# OSD19001_CORE.net
KiCad netlist of a schematic drawn in Altium Designer
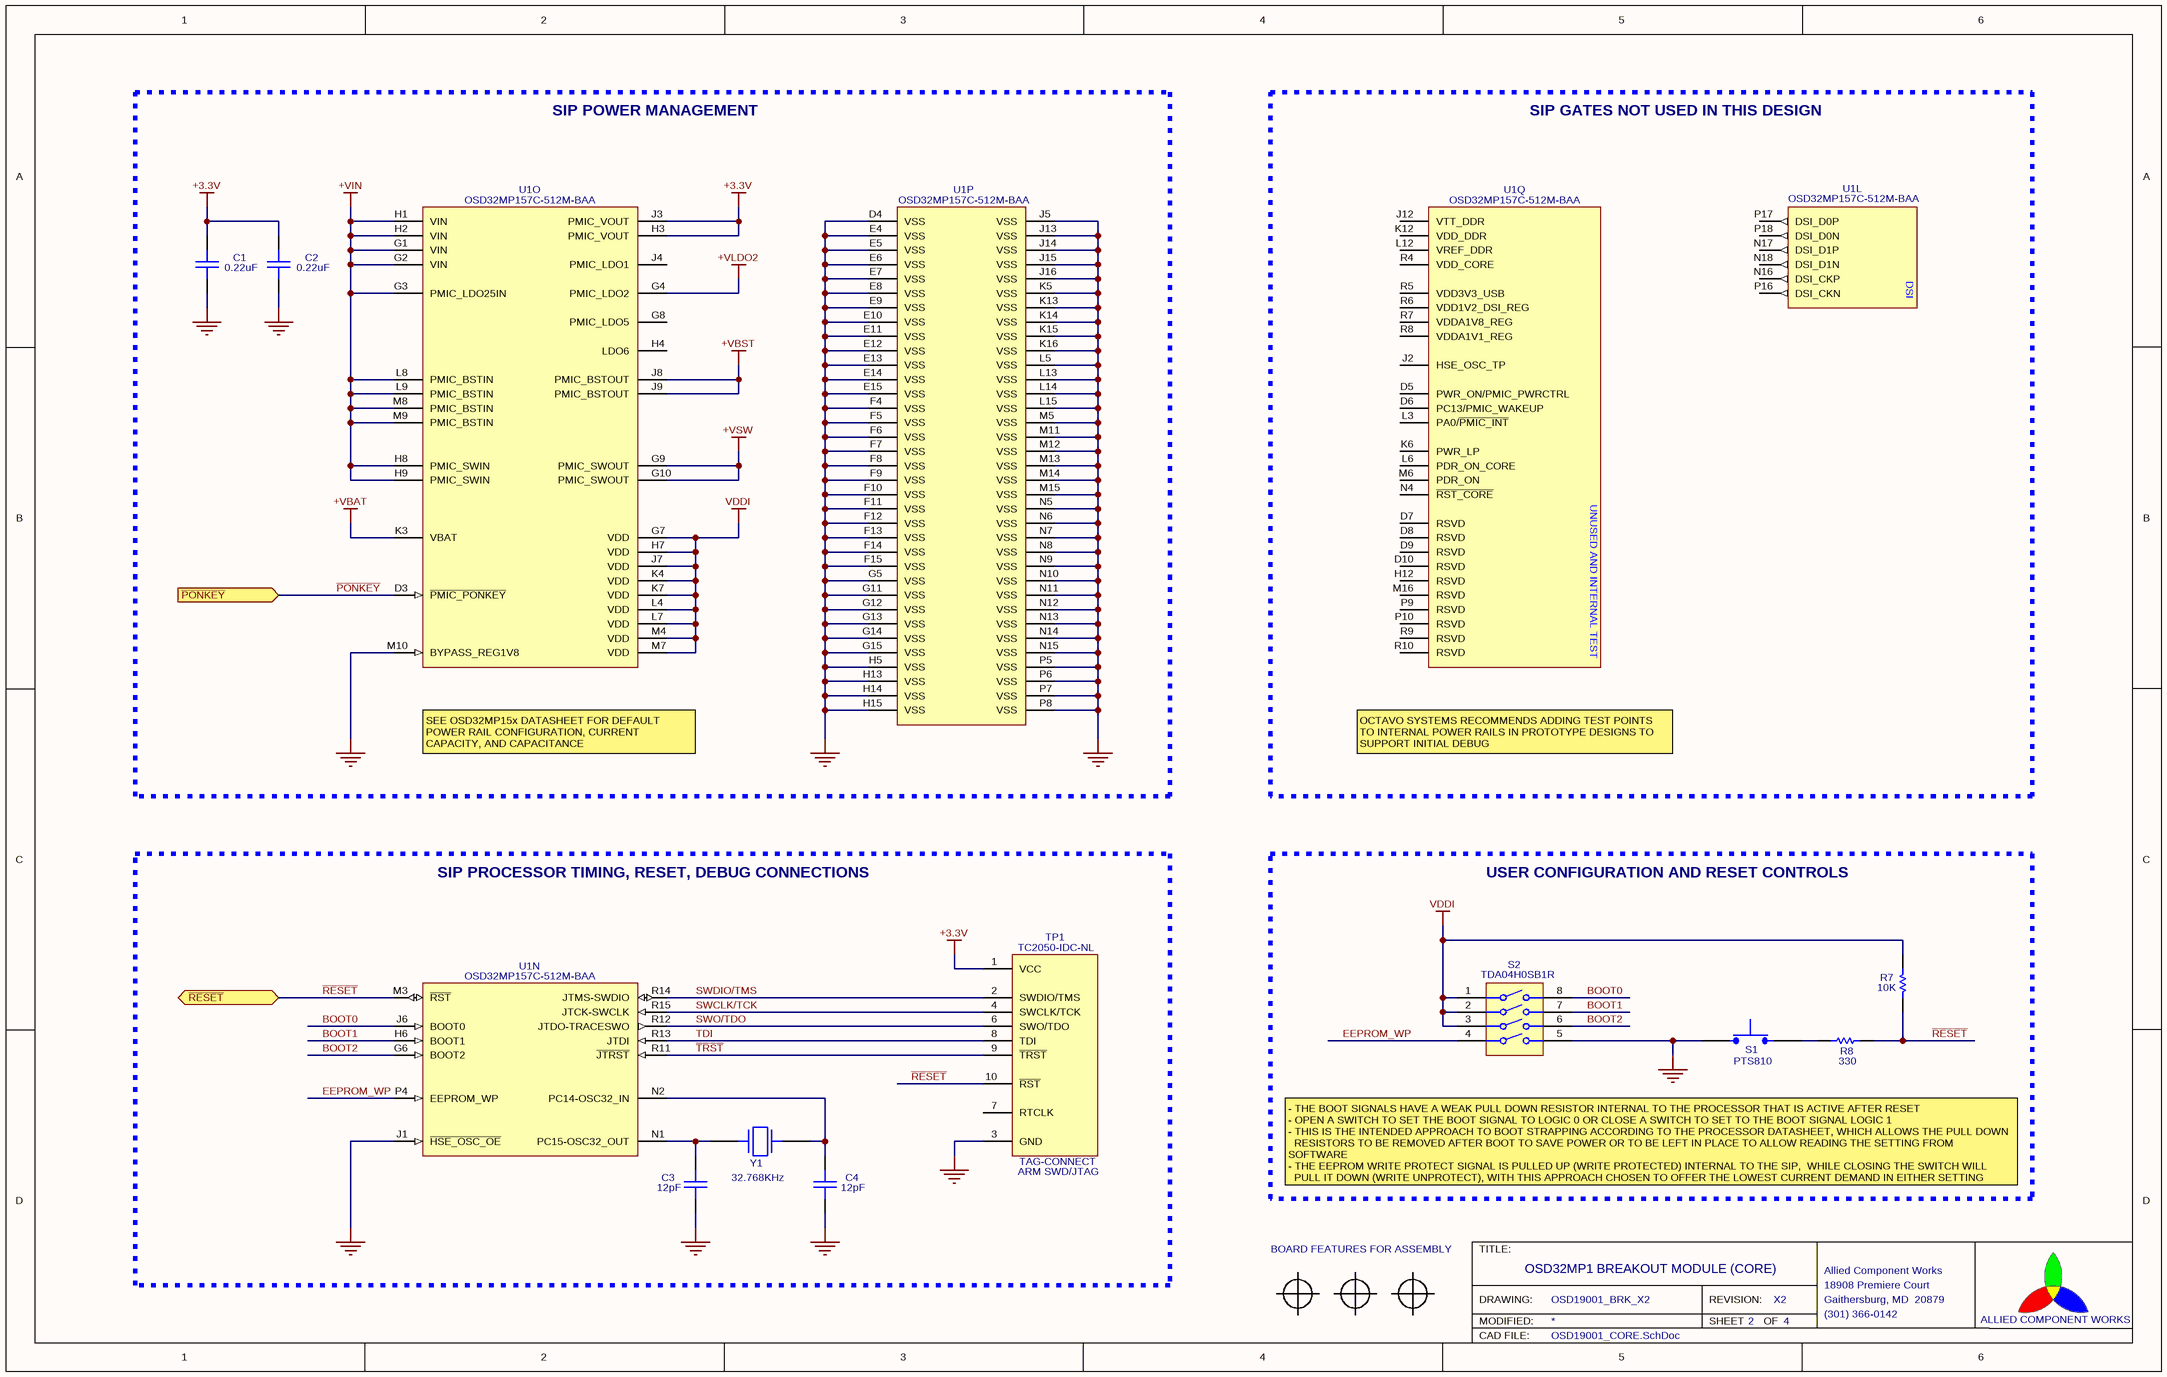
[diagram p0: OSD19001_CORE.SchDoc]

(export (version "E")
  (design (tool "Eeschema 10.0.6"))
  (components
    (comp (ref "C1")
      (value "0.22uF")
      (footprint "LP_0603_HIGH")
      (fields (field (name "TOLERANCE") "10%") (field (name "VOLTAGE") "25V"))
      (libsource (lib "") (part "CERCAP_1"))
    )
    (comp (ref "C2")
      (value "0.22uF")
      (footprint "LP_0603_HIGH")
      (fields (field (name "TOLERANCE") "10%") (field (name "VOLTAGE") "25V"))
      (libsource (lib "") (part "CERCAP_1"))
    )
    (comp (ref "C3")
      (value "12pF")
      (footprint "LP_0402_HIGH")
      (fields (field (name "TOLERANCE") "10%") (field (name "VOLTAGE") "25V"))
      (libsource (lib "ACWPrimitives") (part "CERCAP"))
    )
    (comp (ref "C4")
      (value "12pF")
      (footprint "LP_0402_HIGH")
      (fields (field (name "TOLERANCE") "10%") (field (name "VOLTAGE") "25V"))
      (libsource (lib "ACWPrimitives") (part "CERCAP"))
    )
    (comp (ref "FID1")
      (value "FID")
      (footprint "FID_ROUND_40_TOP")
      (libsource (lib "ACWPrimitives") (part "FIDUCIAL"))
    )
    (comp (ref "FID2")
      (value "FID")
      (footprint "FID_ROUND_40_TOP")
      (libsource (lib "ACWPrimitives") (part "FIDUCIAL"))
    )
    (comp (ref "FID3")
      (value "FID")
      (footprint "FID_ROUND_40_TOP")
      (libsource (lib "ACWPrimitives") (part "FIDUCIAL"))
    )
    (comp (ref "R7")
      (value "10K")
      (footprint "LP_0402_LOW")
      (fields (field (name "TOLERANCE") "5%") (field (name "POWER") "0.1W") (field (name "VOLTAGE") "50V"))
      (libsource (lib "ACWPrimitives") (part "RESISTOR"))
    )
    (comp (ref "R8")
      (value "330")
      (footprint "LP_0402_LOW")
      (fields (field (name "TOLERANCE") "5%") (field (name "POWER") "0.1W") (field (name "VOLTAGE") "50V"))
      (libsource (lib "ACWPrimitives") (part "RESISTOR"))
    )
    (comp (ref "S1")
      (value "PTS810")
      (footprint "C&K_PTS810")
      (description "SPST Tactile Switch, 2 Active Pins")
      (libsource (lib "ACWMisc") (part "TACT_SWITCH"))
    )
    (comp (ref "S2")
      (value "TDA04H0SB1R")
      (footprint "C&K_TDA04")
      (description "Four Position DIP Switch")
      (libsource (lib "ACWMisc") (part "DIP_SW_4"))
    )
    (comp (ref "TP1")
      (value "TC2050-IDC-NL")
      (footprint "TC2050_SITE_NL")
      (description "Tag Connect Site, 10-Pin")
      (libsource (lib "ACWConnectors") (part "TC2050"))
    )
    (comp (ref "U1")
      (value "OSD32MP157C-512M-BAA")
      (footprint "BGA_OCTAVO_SIP_OSD32MP157C")
      (description "Octavo ST Processor SIP")
      (fields (field (name "MANUFACTURER") "Octavo Systems"))
      (libsource (lib "ACWModules") (part "OSD32MP157C"))
    )
    (comp (ref "Y1")
      (value "32.768KHz")
      (footprint "NDK_CRYSTAL_1.5X3.2")
      (description "Crystal")
      (fields (field (name "PARTNUMBER") "NX3215SA-32.768K-STD-MUA-9"))
      (libsource (lib "ACWSemiconductors") (part "CRYSTAL_2PIN"))
    )
  )
  (nets
    (net (code "1") (name "+3.3V") (class "Default")
      (node (ref "C1") (pin "1") (pinfunction "1_1") (pintype "passive"))
      (node (ref "C2") (pin "1") (pinfunction "1_1") (pintype "passive"))
      (node (ref "TP1") (pin "1") (pinfunction "VCC_1") (pintype "passive"))
      (node (ref "U1") (pin "H3") (pinfunction "PMIC_VOUT_H3") (pintype "passive"))
      (node (ref "U1") (pin "J3") (pinfunction "PMIC_VOUT_J3") (pintype "passive"))
    )
    (net (code "2") (name "+VBAT") (class "Default")
      (node (ref "U1") (pin "K3") (pinfunction "VBAT_K3") (pintype "power_in"))
    )
    (net (code "3") (name "+VBST") (class "Default")
      (node (ref "U1") (pin "J8") (pinfunction "PMIC_BSTOUT_J8") (pintype "passive"))
      (node (ref "U1") (pin "J9") (pinfunction "PMIC_BSTOUT_J9") (pintype "passive"))
    )
    (net (code "4") (name "+VIN") (class "Default")
      (node (ref "U1") (pin "G1") (pinfunction "VIN_G1") (pintype "power_in"))
      (node (ref "U1") (pin "G2") (pinfunction "VIN_G2") (pintype "power_in"))
      (node (ref "U1") (pin "G3") (pinfunction "PMIC_LDO25IN_G3") (pintype "power_in"))
      (node (ref "U1") (pin "H1") (pinfunction "VIN_H1") (pintype "power_in"))
      (node (ref "U1") (pin "H2") (pinfunction "VIN_H2") (pintype "power_in"))
      (node (ref "U1") (pin "H8") (pinfunction "PMIC_SWIN_H8") (pintype "passive"))
      (node (ref "U1") (pin "H9") (pinfunction "PMIC_SWIN_H9") (pintype "passive"))
      (node (ref "U1") (pin "L8") (pinfunction "PMIC_BSTIN_L8") (pintype "power_in"))
      (node (ref "U1") (pin "L9") (pinfunction "PMIC_BSTIN_L9") (pintype "power_in"))
      (node (ref "U1") (pin "M8") (pinfunction "PMIC_BSTIN_M8") (pintype "power_in"))
      (node (ref "U1") (pin "M9") (pinfunction "PMIC_BSTIN_M9") (pintype "power_in"))
    )
    (net (code "5") (name "+VLDO2") (class "Default")
      (node (ref "U1") (pin "G4") (pinfunction "PMIC_LDO2_G4") (pintype "passive"))
    )
    (net (code "6") (name "+VSW") (class "Default")
      (node (ref "U1") (pin "G10") (pinfunction "PMIC_SWOUT_G10") (pintype "passive"))
      (node (ref "U1") (pin "G9") (pinfunction "PMIC_SWOUT_G9") (pintype "passive"))
    )
    (net (code "7") (name "/BOOT0") (class "Default")
      (node (ref "S2") (pin "8") (pinfunction "8_8") (pintype "passive"))
      (node (ref "U1") (pin "J6") (pinfunction "BOOT0_J6") (pintype "input"))
    )
    (net (code "8") (name "/BOOT1") (class "Default")
      (node (ref "S2") (pin "7") (pinfunction "7_7") (pintype "passive"))
      (node (ref "U1") (pin "H6") (pinfunction "BOOT1_H6") (pintype "input"))
    )
    (net (code "9") (name "/BOOT2") (class "Default")
      (node (ref "S2") (pin "6") (pinfunction "6_6") (pintype "passive"))
      (node (ref "U1") (pin "G6") (pinfunction "BOOT2_G6") (pintype "input"))
    )
    (net (code "10") (name "/EEPROM_WP") (class "Default")
      (node (ref "S2") (pin "4") (pinfunction "4_4") (pintype "passive"))
      (node (ref "U1") (pin "P4") (pinfunction "EEPROM_WP_P4") (pintype "input"))
    )
    (net (code "11") (name "/PONKEY") (class "Default")
      (node (ref "U1") (pin "D3") (pinfunction "PMIC_PONKEY_D3") (pintype "input"))
    )
    (net (code "12") (name "/RESET") (class "Default")
      (node (ref "R7") (pin "1") (pinfunction "1_1") (pintype "passive"))
      (node (ref "R8") (pin "2") (pinfunction "2_2") (pintype "passive"))
      (node (ref "TP1") (pin "10") (pinfunction "RST_10") (pintype "passive"))
      (node (ref "U1") (pin "M3") (pinfunction "RST_M3") (pintype "bidirectional"))
    )
    (net (code "13") (name "/SWCLK{slash}TCK") (class "Default")
      (node (ref "TP1") (pin "4") (pinfunction "SWCLK/TCK_4") (pintype "passive"))
      (node (ref "U1") (pin "R15") (pinfunction "JTCK-SWCLK_R15") (pintype "input"))
    )
    (net (code "14") (name "/SWDIO{slash}TMS") (class "Default")
      (node (ref "TP1") (pin "2") (pinfunction "SWDIO/TMS_2") (pintype "passive"))
      (node (ref "U1") (pin "R14") (pinfunction "JTMS-SWDIO_R14") (pintype "bidirectional"))
    )
    (net (code "15") (name "/SWO{slash}TDO") (class "Default")
      (node (ref "TP1") (pin "6") (pinfunction "SWO/TDO_6") (pintype "passive"))
      (node (ref "U1") (pin "R12") (pinfunction "JTDO-TRACESWO_R12") (pintype "output"))
    )
    (net (code "16") (name "/TDI") (class "Default")
      (node (ref "TP1") (pin "8") (pinfunction "TDI_8") (pintype "passive"))
      (node (ref "U1") (pin "R13") (pinfunction "JTDI_R13") (pintype "input"))
    )
    (net (code "17") (name "/TRST") (class "Default")
      (node (ref "TP1") (pin "9") (pinfunction "TRST_9") (pintype "passive"))
      (node (ref "U1") (pin "R11") (pinfunction "JTRST_R11") (pintype "input"))
    )
    (net (code "18") (name "GND") (class "Default")
      (node (ref "C1") (pin "2") (pinfunction "2_2") (pintype "passive"))
      (node (ref "C2") (pin "2") (pinfunction "2_2") (pintype "passive"))
      (node (ref "C3") (pin "2") (pinfunction "2_2") (pintype "passive"))
      (node (ref "C4") (pin "2") (pinfunction "2_2") (pintype "passive"))
      (node (ref "S1") (pin "2") (pinfunction "2_2") (pintype "passive"))
      (node (ref "S2") (pin "5") (pinfunction "5_5") (pintype "passive"))
      (node (ref "TP1") (pin "3") (pinfunction "GND_3") (pintype "passive"))
      (node (ref "U1") (pin "D4") (pinfunction "VSS_D4") (pintype "power_in"))
      (node (ref "U1") (pin "E10") (pinfunction "VSS_E10") (pintype "power_in"))
      (node (ref "U1") (pin "E11") (pinfunction "VSS_E11") (pintype "power_in"))
      (node (ref "U1") (pin "E12") (pinfunction "VSS_E12") (pintype "power_in"))
      (node (ref "U1") (pin "E13") (pinfunction "VSS_E13") (pintype "power_in"))
      (node (ref "U1") (pin "E14") (pinfunction "VSS_E14") (pintype "power_in"))
      (node (ref "U1") (pin "E15") (pinfunction "VSS_E15") (pintype "power_in"))
      (node (ref "U1") (pin "E4") (pinfunction "VSS_E4") (pintype "power_in"))
      (node (ref "U1") (pin "E5") (pinfunction "VSS_E5") (pintype "power_in"))
      (node (ref "U1") (pin "E6") (pinfunction "VSS_E6") (pintype "power_in"))
      (node (ref "U1") (pin "E7") (pinfunction "VSS_E7") (pintype "power_in"))
      (node (ref "U1") (pin "E8") (pinfunction "VSS_E8") (pintype "power_in"))
      (node (ref "U1") (pin "E9") (pinfunction "VSS_E9") (pintype "power_in"))
      (node (ref "U1") (pin "F10") (pinfunction "VSS_F10") (pintype "power_in"))
      (node (ref "U1") (pin "F11") (pinfunction "VSS_F11") (pintype "power_in"))
      (node (ref "U1") (pin "F12") (pinfunction "VSS_F12") (pintype "power_in"))
      (node (ref "U1") (pin "F13") (pinfunction "VSS_F13") (pintype "power_in"))
      (node (ref "U1") (pin "F14") (pinfunction "VSS_F14") (pintype "power_in"))
      (node (ref "U1") (pin "F15") (pinfunction "VSS_F15") (pintype "power_in"))
      (node (ref "U1") (pin "F4") (pinfunction "VSS_F4") (pintype "power_in"))
      (node (ref "U1") (pin "F5") (pinfunction "VSS_F5") (pintype "power_in"))
      (node (ref "U1") (pin "F6") (pinfunction "VSS_F6") (pintype "power_in"))
      (node (ref "U1") (pin "F7") (pinfunction "VSS_F7") (pintype "power_in"))
      (node (ref "U1") (pin "F8") (pinfunction "VSS_F8") (pintype "power_in"))
      (node (ref "U1") (pin "F9") (pinfunction "VSS_F9") (pintype "power_in"))
      (node (ref "U1") (pin "G11") (pinfunction "VSS_G11") (pintype "power_in"))
      (node (ref "U1") (pin "G12") (pinfunction "VSS_G12") (pintype "power_in"))
      (node (ref "U1") (pin "G13") (pinfunction "VSS_G13") (pintype "power_in"))
      (node (ref "U1") (pin "G14") (pinfunction "VSS_G14") (pintype "power_in"))
      (node (ref "U1") (pin "G15") (pinfunction "VSS_G15") (pintype "power_in"))
      (node (ref "U1") (pin "G5") (pinfunction "VSS_G5") (pintype "power_in"))
      (node (ref "U1") (pin "H13") (pinfunction "VSS_H13") (pintype "power_in"))
      (node (ref "U1") (pin "H14") (pinfunction "VSS_H14") (pintype "power_in"))
      (node (ref "U1") (pin "H15") (pinfunction "VSS_H15") (pintype "power_in"))
      (node (ref "U1") (pin "H5") (pinfunction "VSS_H5") (pintype "power_in"))
      (node (ref "U1") (pin "J1") (pinfunction "HSE_OSC_OE_J1") (pintype "input"))
      (node (ref "U1") (pin "J13") (pinfunction "VSS_J13") (pintype "power_in"))
      (node (ref "U1") (pin "J14") (pinfunction "VSS_J14") (pintype "power_in"))
      (node (ref "U1") (pin "J15") (pinfunction "VSS_J15") (pintype "power_in"))
      (node (ref "U1") (pin "J16") (pinfunction "VSS_J16") (pintype "power_in"))
      (node (ref "U1") (pin "J5") (pinfunction "VSS_J5") (pintype "power_in"))
      (node (ref "U1") (pin "K13") (pinfunction "VSS_K13") (pintype "power_in"))
      (node (ref "U1") (pin "K14") (pinfunction "VSS_K14") (pintype "power_in"))
      (node (ref "U1") (pin "K15") (pinfunction "VSS_K15") (pintype "power_in"))
      (node (ref "U1") (pin "K16") (pinfunction "VSS_K16") (pintype "power_in"))
      (node (ref "U1") (pin "K5") (pinfunction "VSS_K5") (pintype "power_in"))
      (node (ref "U1") (pin "L13") (pinfunction "VSS_L13") (pintype "power_in"))
      (node (ref "U1") (pin "L14") (pinfunction "VSS_L14") (pintype "power_in"))
      (node (ref "U1") (pin "L15") (pinfunction "VSS_L15") (pintype "power_in"))
      (node (ref "U1") (pin "L5") (pinfunction "VSS_L5") (pintype "power_in"))
      (node (ref "U1") (pin "M10") (pinfunction "BYPASS_REG1V8_M10") (pintype "input"))
      (node (ref "U1") (pin "M11") (pinfunction "VSS_M11") (pintype "power_in"))
      (node (ref "U1") (pin "M12") (pinfunction "VSS_M12") (pintype "power_in"))
      (node (ref "U1") (pin "M13") (pinfunction "VSS_M13") (pintype "power_in"))
      (node (ref "U1") (pin "M14") (pinfunction "VSS_M14") (pintype "power_in"))
      (node (ref "U1") (pin "M15") (pinfunction "VSS_M15") (pintype "power_in"))
      (node (ref "U1") (pin "M5") (pinfunction "VSS_M5") (pintype "power_in"))
      (node (ref "U1") (pin "N10") (pinfunction "VSS_N10") (pintype "power_in"))
      (node (ref "U1") (pin "N11") (pinfunction "VSS_N11") (pintype "power_in"))
      (node (ref "U1") (pin "N12") (pinfunction "VSS_N12") (pintype "power_in"))
      (node (ref "U1") (pin "N13") (pinfunction "VSS_N13") (pintype "power_in"))
      (node (ref "U1") (pin "N14") (pinfunction "VSS_N14") (pintype "power_in"))
      (node (ref "U1") (pin "N15") (pinfunction "VSS_N15") (pintype "power_in"))
      (node (ref "U1") (pin "N5") (pinfunction "VSS_N5") (pintype "power_in"))
      (node (ref "U1") (pin "N6") (pinfunction "VSS_N6") (pintype "power_in"))
      (node (ref "U1") (pin "N7") (pinfunction "VSS_N7") (pintype "power_in"))
      (node (ref "U1") (pin "N8") (pinfunction "VSS_N8") (pintype "power_in"))
      (node (ref "U1") (pin "N9") (pinfunction "VSS_N9") (pintype "power_in"))
      (node (ref "U1") (pin "P5") (pinfunction "VSS_P5") (pintype "power_in"))
      (node (ref "U1") (pin "P6") (pinfunction "VSS_P6") (pintype "power_in"))
      (node (ref "U1") (pin "P7") (pinfunction "VSS_P7") (pintype "power_in"))
      (node (ref "U1") (pin "P8") (pinfunction "VSS_P8") (pintype "power_in"))
    )
    (net (code "19") (name "Net-(R8-Pad1)") (class "Default")
      (node (ref "R8") (pin "1") (pinfunction "1_1") (pintype "passive"))
      (node (ref "S1") (pin "1") (pinfunction "1_1") (pintype "passive"))
    )
    (net (code "20") (name "Net-(U1N-PC14-OSC32_IN)") (class "Default")
      (node (ref "C4") (pin "1") (pinfunction "1_1") (pintype "passive"))
      (node (ref "U1") (pin "N2") (pinfunction "PC14-OSC32_IN_N2") (pintype "passive"))
      (node (ref "Y1") (pin "1") (pinfunction "1_1") (pintype "passive"))
    )
    (net (code "21") (name "Net-(U1N-PC15-OSC32_OUT)") (class "Default")
      (node (ref "C3") (pin "1") (pinfunction "1_1") (pintype "passive"))
      (node (ref "U1") (pin "N1") (pinfunction "PC15-OSC32_OUT_N1") (pintype "passive"))
      (node (ref "Y1") (pin "2") (pinfunction "2_2") (pintype "passive"))
    )
    (net (code "22") (name "VDDI") (class "Default")
      (node (ref "R7") (pin "2") (pinfunction "2_2") (pintype "passive"))
      (node (ref "S2") (pin "1") (pinfunction "1_1") (pintype "passive"))
      (node (ref "S2") (pin "2") (pinfunction "2_2") (pintype "passive"))
      (node (ref "S2") (pin "3") (pinfunction "3_3") (pintype "passive"))
      (node (ref "U1") (pin "G7") (pinfunction "VDD_G7") (pintype "passive"))
      (node (ref "U1") (pin "H7") (pinfunction "VDD_H7") (pintype "passive"))
      (node (ref "U1") (pin "J7") (pinfunction "VDD_J7") (pintype "passive"))
      (node (ref "U1") (pin "K4") (pinfunction "VDD_K4") (pintype "passive"))
      (node (ref "U1") (pin "K7") (pinfunction "VDD_K7") (pintype "passive"))
      (node (ref "U1") (pin "L4") (pinfunction "VDD_L4") (pintype "passive"))
      (node (ref "U1") (pin "L7") (pinfunction "VDD_L7") (pintype "passive"))
      (node (ref "U1") (pin "M4") (pinfunction "VDD_M4") (pintype "passive"))
      (node (ref "U1") (pin "M7") (pinfunction "VDD_M7") (pintype "passive"))
    )
    (net (code "23") (name "unconnected-(TP1-RTCLK-Pad7)") (class "Default")
      (node (ref "TP1") (pin "7") (pinfunction "RTCLK_7") (pintype "passive"))
    )
    (net (code "24") (name "unconnected-(U1L-DSI_CKN-PadP16)") (class "Default")
      (node (ref "U1") (pin "P16") (pinfunction "DSI_CKN_P16") (pintype "output"))
    )
    (net (code "25") (name "unconnected-(U1L-DSI_CKP-PadN16)") (class "Default")
      (node (ref "U1") (pin "N16") (pinfunction "DSI_CKP_N16") (pintype "output"))
    )
    (net (code "26") (name "unconnected-(U1L-DSI_D0N-PadP18)") (class "Default")
      (node (ref "U1") (pin "P18") (pinfunction "DSI_D0N_P18") (pintype "output"))
    )
    (net (code "27") (name "unconnected-(U1L-DSI_D0P-PadP17)") (class "Default")
      (node (ref "U1") (pin "P17") (pinfunction "DSI_D0P_P17") (pintype "output"))
    )
    (net (code "28") (name "unconnected-(U1L-DSI_D1N-PadN18)") (class "Default")
      (node (ref "U1") (pin "N18") (pinfunction "DSI_D1N_N18") (pintype "output"))
    )
    (net (code "29") (name "unconnected-(U1L-DSI_D1P-PadN17)") (class "Default")
      (node (ref "U1") (pin "N17") (pinfunction "DSI_D1P_N17") (pintype "output"))
    )
    (net (code "30") (name "unconnected-(U1O-LDO6-PadH4)") (class "Default")
      (node (ref "U1") (pin "H4") (pinfunction "LDO6_H4") (pintype "passive"))
    )
    (net (code "31") (name "unconnected-(U1O-PMIC_LDO1-PadJ4)") (class "Default")
      (node (ref "U1") (pin "J4") (pinfunction "PMIC_LDO1_J4") (pintype "passive"))
    )
    (net (code "32") (name "unconnected-(U1O-PMIC_LDO5-PadG8)") (class "Default")
      (node (ref "U1") (pin "G8") (pinfunction "PMIC_LDO5_G8") (pintype "passive"))
    )
    (net (code "33") (name "unconnected-(U1Q-HSE_OSC_TP-PadJ2)") (class "Default")
      (node (ref "U1") (pin "J2") (pinfunction "HSE_OSC_TP_J2") (pintype "passive"))
    )
    (net (code "34") (name "unconnected-(U1Q-PA0{slash}~{PMIC_INT}-PadL3)") (class "Default")
      (node (ref "U1") (pin "L3") (pinfunction "PA0/~{PMIC_INT}_L3") (pintype "passive"))
    )
    (net (code "35") (name "unconnected-(U1Q-PC13{slash}PMIC_WAKEUP-PadD6)") (class "Default")
      (node (ref "U1") (pin "D6") (pinfunction "PC13/PMIC_WAKEUP_D6") (pintype "passive"))
    )
    (net (code "36") (name "unconnected-(U1Q-PDR_ON-PadM6)") (class "Default")
      (node (ref "U1") (pin "M6") (pinfunction "PDR_ON_M6") (pintype "passive"))
    )
    (net (code "37") (name "unconnected-(U1Q-PDR_ON_CORE-PadL6)") (class "Default")
      (node (ref "U1") (pin "L6") (pinfunction "PDR_ON_CORE_L6") (pintype "passive"))
    )
    (net (code "38") (name "unconnected-(U1Q-PWR_LP-PadK6)") (class "Default")
      (node (ref "U1") (pin "K6") (pinfunction "PWR_LP_K6") (pintype "passive"))
    )
    (net (code "39") (name "unconnected-(U1Q-PWR_ON{slash}PMIC_PWRCTRL-PadD5)") (class "Default")
      (node (ref "U1") (pin "D5") (pinfunction "PWR_ON/PMIC_PWRCTRL_D5") (pintype "passive"))
    )
    (net (code "40") (name "unconnected-(U1Q-RST_CORE-PadN4)") (class "Default")
      (node (ref "U1") (pin "N4") (pinfunction "RST_CORE_N4") (pintype "passive"))
    )
    (net (code "41") (name "unconnected-(U1Q-RSVD-PadD7)") (class "Default")
      (node (ref "U1") (pin "D7") (pinfunction "RSVD_D7") (pintype "passive"))
    )
    (net (code "42") (name "unconnected-(U1Q-RSVD-PadD8)") (class "Default")
      (node (ref "U1") (pin "D8") (pinfunction "RSVD_D8") (pintype "passive"))
    )
    (net (code "43") (name "unconnected-(U1Q-RSVD-PadD9)") (class "Default")
      (node (ref "U1") (pin "D9") (pinfunction "RSVD_D9") (pintype "passive"))
    )
    (net (code "44") (name "unconnected-(U1Q-RSVD-PadD10)") (class "Default")
      (node (ref "U1") (pin "D10") (pinfunction "RSVD_D10") (pintype "passive"))
    )
    (net (code "45") (name "unconnected-(U1Q-RSVD-PadH12)") (class "Default")
      (node (ref "U1") (pin "H12") (pinfunction "RSVD_H12") (pintype "passive"))
    )
    (net (code "46") (name "unconnected-(U1Q-RSVD-PadM16)") (class "Default")
      (node (ref "U1") (pin "M16") (pinfunction "RSVD_M16") (pintype "passive"))
    )
    (net (code "47") (name "unconnected-(U1Q-RSVD-PadP9)") (class "Default")
      (node (ref "U1") (pin "P9") (pinfunction "RSVD_P9") (pintype "passive"))
    )
    (net (code "48") (name "unconnected-(U1Q-RSVD-PadP10)") (class "Default")
      (node (ref "U1") (pin "P10") (pinfunction "RSVD_P10") (pintype "passive"))
    )
    (net (code "49") (name "unconnected-(U1Q-RSVD-PadR9)") (class "Default")
      (node (ref "U1") (pin "R9") (pinfunction "RSVD_R9") (pintype "passive"))
    )
    (net (code "50") (name "unconnected-(U1Q-RSVD-PadR10)") (class "Default")
      (node (ref "U1") (pin "R10") (pinfunction "RSVD_R10") (pintype "passive"))
    )
    (net (code "51") (name "unconnected-(U1Q-VDD1V2_DSI_REG-PadR6)") (class "Default")
      (node (ref "U1") (pin "R6") (pinfunction "VDD1V2_DSI_REG_R6") (pintype "passive"))
    )
    (net (code "52") (name "unconnected-(U1Q-VDD3V3_USB-PadR5)") (class "Default")
      (node (ref "U1") (pin "R5") (pinfunction "VDD3V3_USB_R5") (pintype "passive"))
    )
    (net (code "53") (name "unconnected-(U1Q-VDDA1V1_REG-PadR8)") (class "Default")
      (node (ref "U1") (pin "R8") (pinfunction "VDDA1V1_REG_R8") (pintype "passive"))
    )
    (net (code "54") (name "unconnected-(U1Q-VDDA1V8_REG-PadR7)") (class "Default")
      (node (ref "U1") (pin "R7") (pinfunction "VDDA1V8_REG_R7") (pintype "passive"))
    )
    (net (code "55") (name "unconnected-(U1Q-VDD_CORE-PadR4)") (class "Default")
      (node (ref "U1") (pin "R4") (pinfunction "VDD_CORE_R4") (pintype "passive"))
    )
    (net (code "56") (name "unconnected-(U1Q-VDD_DDR-PadK12)") (class "Default")
      (node (ref "U1") (pin "K12") (pinfunction "VDD_DDR_K12") (pintype "passive"))
    )
    (net (code "57") (name "unconnected-(U1Q-VREF_DDR-PadL12)") (class "Default")
      (node (ref "U1") (pin "L12") (pinfunction "VREF_DDR_L12") (pintype "passive"))
    )
    (net (code "58") (name "unconnected-(U1Q-VTT_DDR-PadJ12)") (class "Default")
      (node (ref "U1") (pin "J12") (pinfunction "VTT_DDR_J12") (pintype "passive"))
    )
  )
)
